# greenhousectrl-latest-monday-redo.net
KiCad netlist of a schematic drawn in EAGLE
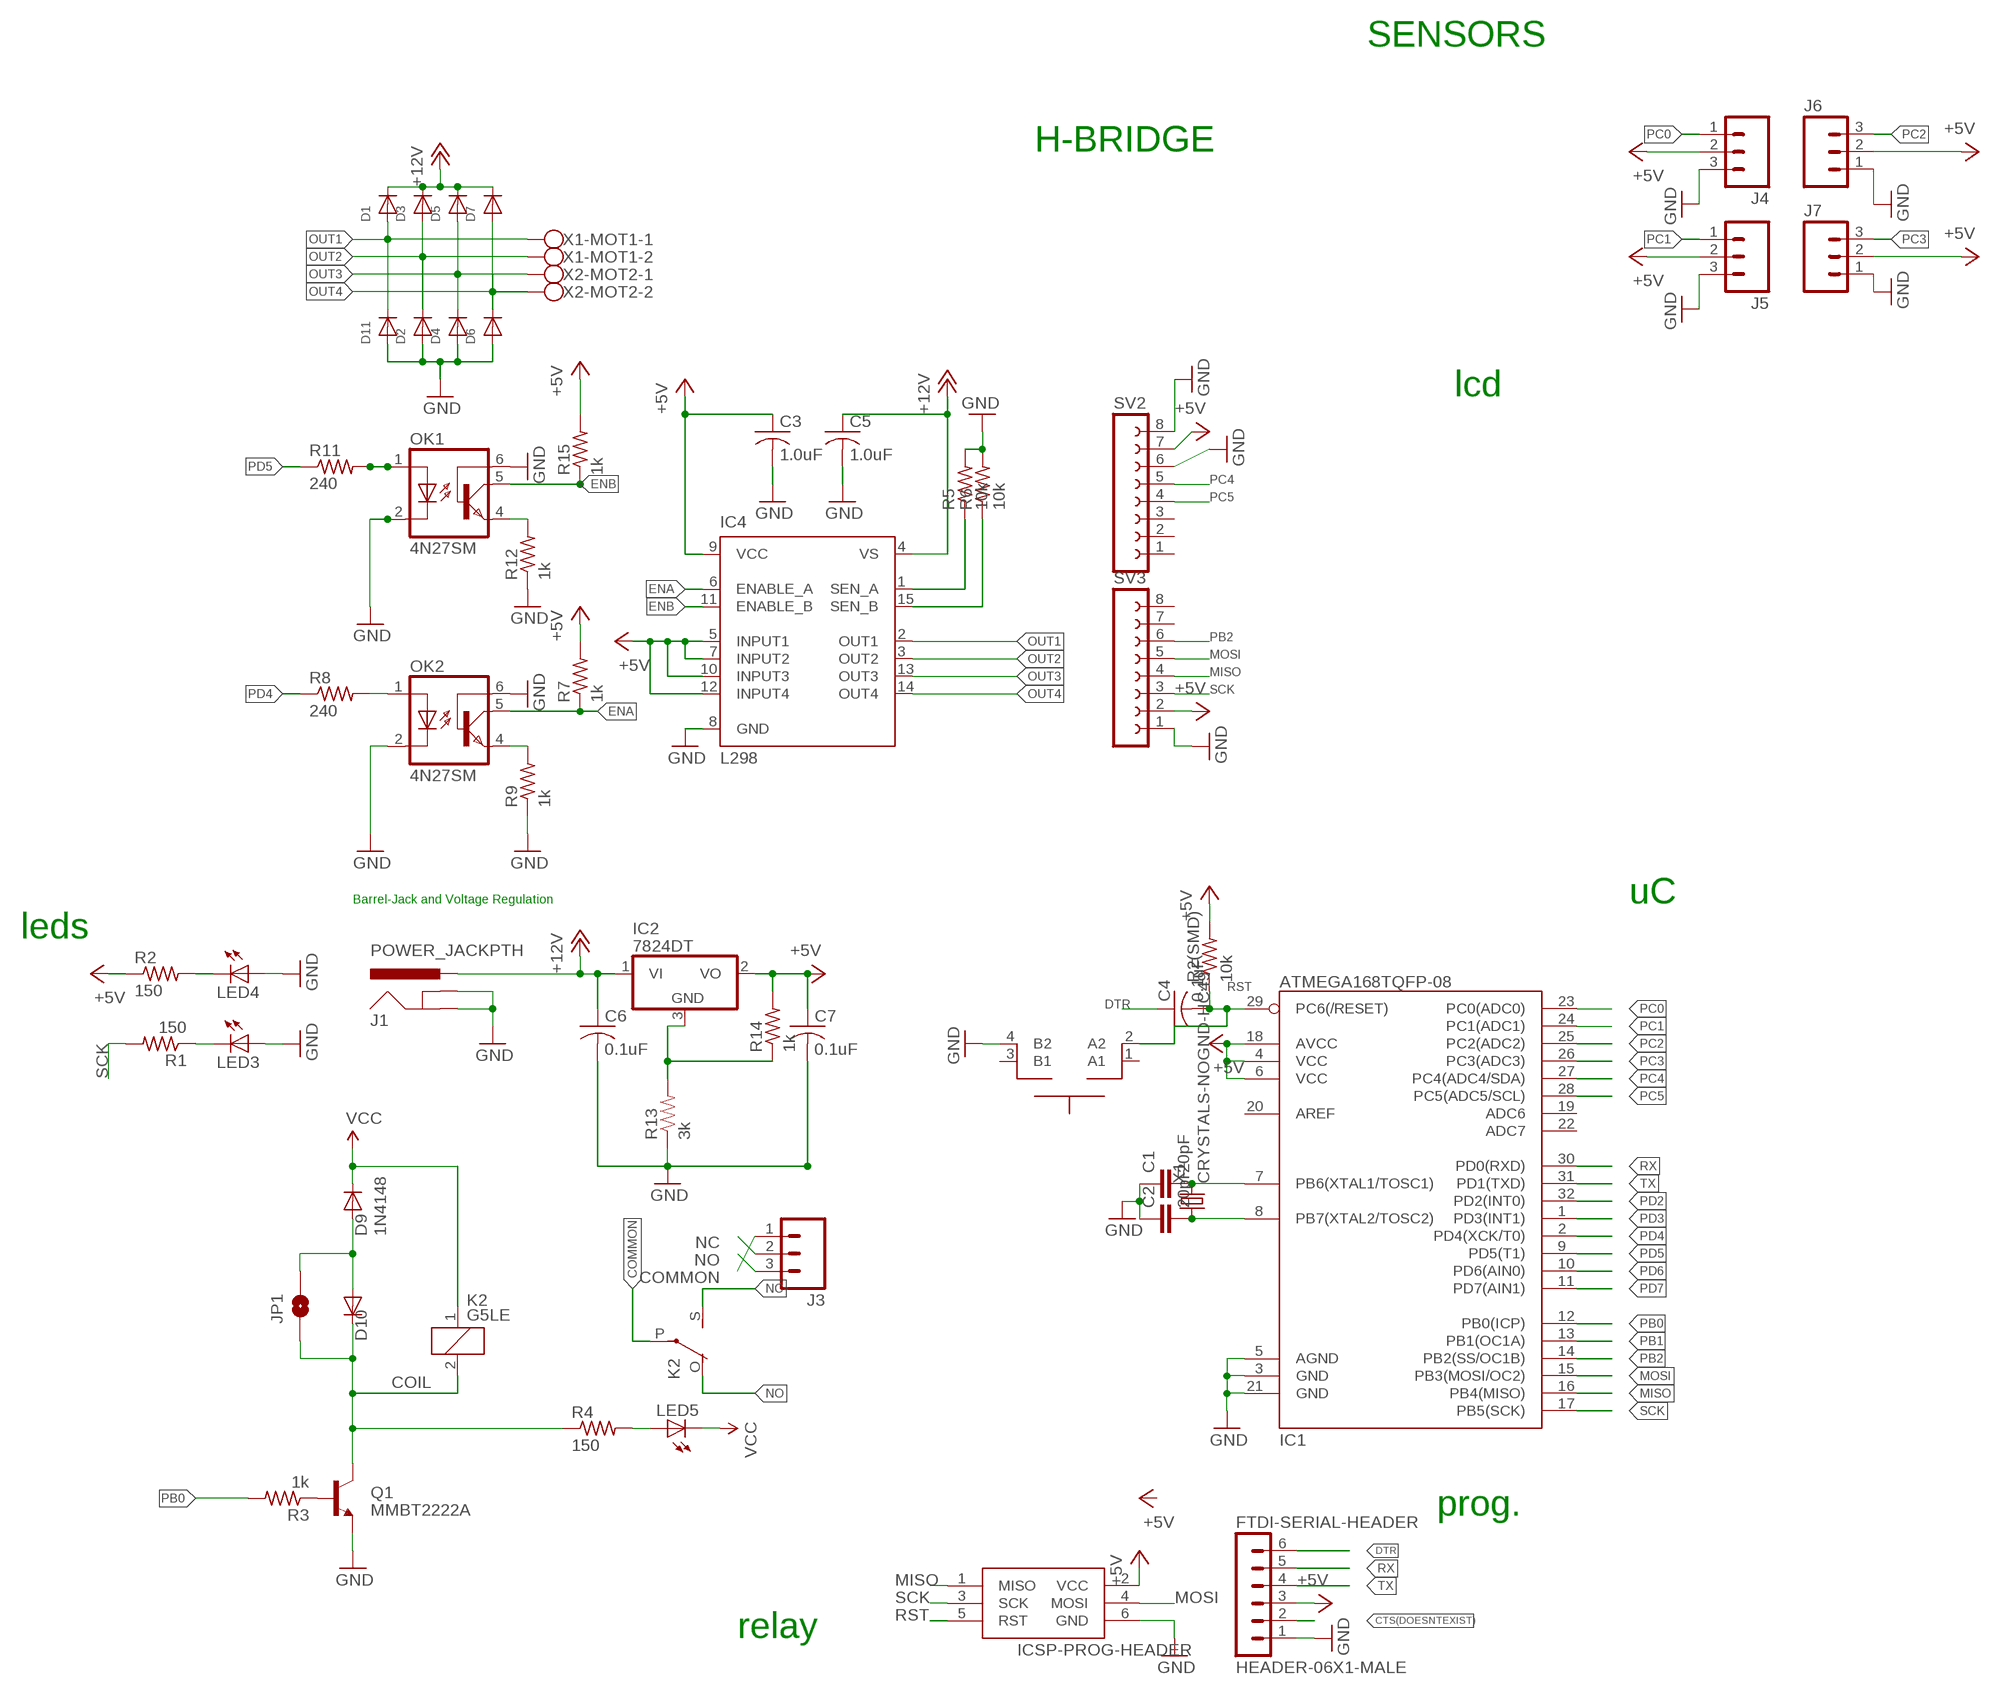
[diagram p0: schematic, sheet 1]

(export (version "E")
  (design (tool "Eeschema 10.0.6"))
  (components
    (comp (ref "C1")
      (value "20pF")
      (footprint "eagle-import:C0805")
      (libsource (lib "eagle-import") (part "C-EUC0805"))
    )
    (comp (ref "C2")
      (value "20pF")
      (footprint "eagle-import:C0805")
      (libsource (lib "eagle-import") (part "C-EUC0805"))
    )
    (comp (ref "C3")
      (value "1.0uF")
      (footprint "eagle-import:C0805")
      (libsource (lib "eagle-import") (part "C-USC0805"))
    )
    (comp (ref "C4")
      (value "0.1uF")
      (footprint "eagle-import:C0805")
      (libsource (lib "eagle-import") (part "C-USC0805"))
    )
    (comp (ref "C5")
      (value "1.0uF")
      (footprint "eagle-import:C0805")
      (libsource (lib "eagle-import") (part "C-USC0805"))
    )
    (comp (ref "C6")
      (value "0.1uF")
      (footprint "eagle-import:C0805")
      (libsource (lib "eagle-import") (part "C-USC0805"))
    )
    (comp (ref "C7")
      (value "0.1uF")
      (footprint "eagle-import:C0805")
      (libsource (lib "eagle-import") (part "C-USC0805"))
    )
    (comp (ref "D1")
      (value "DIODESOD-523")
      (footprint "eagle-import:SOD-523")
      (libsource (lib "eagle-import") (part "DIODESOD-523"))
    )
    (comp (ref "D2")
      (value "DIODESOD-523")
      (footprint "eagle-import:SOD-523")
      (libsource (lib "eagle-import") (part "DIODESOD-523"))
    )
    (comp (ref "D3")
      (value "DIODESOD-523")
      (footprint "eagle-import:SOD-523")
      (libsource (lib "eagle-import") (part "DIODESOD-523"))
    )
    (comp (ref "D4")
      (value "DIODESOD-523")
      (footprint "eagle-import:SOD-523")
      (libsource (lib "eagle-import") (part "DIODESOD-523"))
    )
    (comp (ref "D5")
      (value "DIODESOD-523")
      (footprint "eagle-import:SOD-523")
      (libsource (lib "eagle-import") (part "DIODESOD-523"))
    )
    (comp (ref "D6")
      (value "DIODESOD-523")
      (footprint "eagle-import:SOD-523")
      (libsource (lib "eagle-import") (part "DIODESOD-523"))
    )
    (comp (ref "D7")
      (value "DIODESOD-523")
      (footprint "eagle-import:SOD-523")
      (libsource (lib "eagle-import") (part "DIODESOD-523"))
    )
    (comp (ref "D9")
      (value "1N4148")
      (footprint "eagle-import:SOD-323F")
      (libsource (lib "eagle-import") (part "DIODESOD-323F"))
    )
    (comp (ref "D10")
      (value "Zener")
      (footprint "eagle-import:SOD-323F")
      (libsource (lib "eagle-import") (part "DIODESOD-323F"))
    )
    (comp (ref "D11")
      (value "DIODESOD-523")
      (footprint "eagle-import:SOD-523")
      (libsource (lib "eagle-import") (part "DIODESOD-523"))
    )
    (comp (ref "FTDI-SERIAL-HEADER")
      (value "HEADER-06X1-MALE")
      (footprint "eagle-import:06X1-PTH")
      (libsource (lib "eagle-import") (part "HEADER-06X1?-MALE"))
    )
    (comp (ref "IC1")
      (value "ATMEGA168TQFP-08")
      (footprint "eagle-import:TQFP32-08")
      (libsource (lib "eagle-import") (part "ATMEGA168TQFP-08"))
    )
    (comp (ref "IC2")
      (value "7824DT")
      (footprint "eagle-import:TO252")
      (libsource (lib "eagle-import") (part "78DT24"))
    )
    (comp (ref "IC4")
      (value "L298")
      (footprint "eagle-import:MULTIWATT-15")
      (fields (field (name "MPN") "L298N"))
      (libsource (lib "eagle-import") (part "L298"))
    )
    (comp (ref "ICSP-PROG-HEADER")
      (value "AVRISP-6")
      (footprint "eagle-import:AVRISP")
      (libsource (lib "eagle-import") (part "AVRISP-6"))
    )
    (comp (ref "J1")
      (value "POWER_JACKPTH")
      (footprint "eagle-import:POWER_JACK_PTH")
      (libsource (lib "eagle-import") (part "POWER_JACKPTH"))
    )
    (comp (ref "J3")
      (value "M03-SCREW-5MM")
      (footprint "eagle-import:SCREWTERMINAL-5MM-3")
      (libsource (lib "eagle-import") (part "M03-SCREW-5MM"))
    )
    (comp (ref "J4")
      (value "M03SCREW_LOCK")
      (footprint "eagle-import:SCREWTERMINAL-3.5MM-3_LOCK.007S")
      (libsource (lib "eagle-import") (part "M03SCREW_LOCK"))
    )
    (comp (ref "J5")
      (value "M03SCREW_LOCK")
      (footprint "eagle-import:SCREWTERMINAL-3.5MM-3_LOCK.007S")
      (libsource (lib "eagle-import") (part "M03SCREW_LOCK"))
    )
    (comp (ref "J6")
      (value "M03SCREW_LOCK")
      (footprint "eagle-import:SCREWTERMINAL-3.5MM-3_LOCK.007S")
      (libsource (lib "eagle-import") (part "M03SCREW_LOCK"))
    )
    (comp (ref "J7")
      (value "M03SCREW_LOCK")
      (footprint "eagle-import:SCREWTERMINAL-3.5MM-3_LOCK.007S")
      (libsource (lib "eagle-import") (part "M03SCREW_LOCK"))
    )
    (comp (ref "JP1")
      (value "JUMPER-PAD-2-NOYES_SILK")
      (footprint "eagle-import:PAD-JUMPER-2-NO_YES_SILK")
      (libsource (lib "eagle-import") (part "JUMPER-PAD-2-NOYES_SILK"))
    )
    (comp (ref "K2")
      (value "G5LE")
      (footprint "eagle-import:G5LE")
      (libsource (lib "eagle-import") (part "G5LE"))
    )
    (comp (ref "LED3")
      (value "LEDCHIP-LED0805")
      (footprint "eagle-import:CHIP-LED0805")
      (libsource (lib "eagle-import") (part "LEDCHIP-LED0805"))
    )
    (comp (ref "LED4")
      (value "LEDCHIP-LED0805")
      (footprint "eagle-import:CHIP-LED0805")
      (libsource (lib "eagle-import") (part "LEDCHIP-LED0805"))
    )
    (comp (ref "LED5")
      (value "LEDCHIP-LED0805")
      (footprint "eagle-import:CHIP-LED0805")
      (libsource (lib "eagle-import") (part "LEDCHIP-LED0805"))
    )
    (comp (ref "OK1")
      (value "4N27SM")
      (footprint "eagle-import:DIL6-SMD")
      (fields (field (name "MF") "FAIRCHILD SEMICONDUCTOR") (field (name "MPN") "4N27S-M"))
      (libsource (lib "eagle-import") (part "4N?MS27"))
    )
    (comp (ref "OK2")
      (value "4N27SM")
      (footprint "eagle-import:DIL6-SMD")
      (fields (field (name "MF") "FAIRCHILD SEMICONDUCTOR") (field (name "MPN") "4N27S-M"))
      (libsource (lib "eagle-import") (part "4N?MS27"))
    )
    (comp (ref "Q1")
      (value "MMBT2222A")
      (footprint "eagle-import:SOT23-3")
      (libsource (lib "eagle-import") (part "TRANSISTOR_NPNMMBT2222A"))
    )
    (comp (ref "R1")
      (value "150")
      (footprint "eagle-import:M0805")
      (libsource (lib "eagle-import") (part "R-US_M0805"))
    )
    (comp (ref "R2")
      (value "150")
      (footprint "eagle-import:M0805")
      (libsource (lib "eagle-import") (part "R-US_M0805"))
    )
    (comp (ref "R2(SMD)")
      (value "10k")
      (footprint "eagle-import:M0805")
      (libsource (lib "eagle-import") (part "R-US_M0805"))
    )
    (comp (ref "R3")
      (value "1k")
      (footprint "eagle-import:M0805")
      (libsource (lib "eagle-import") (part "R-US_M0805"))
    )
    (comp (ref "R4")
      (value "150")
      (footprint "eagle-import:M0805")
      (libsource (lib "eagle-import") (part "R-US_M0805"))
    )
    (comp (ref "R5")
      (value "10k")
      (footprint "eagle-import:M0805")
      (libsource (lib "eagle-import") (part "R-US_M0805"))
    )
    (comp (ref "R6")
      (value "10k")
      (footprint "eagle-import:M0805")
      (libsource (lib "eagle-import") (part "R-US_M0805"))
    )
    (comp (ref "R7")
      (value "1k")
      (footprint "eagle-import:M0805")
      (libsource (lib "eagle-import") (part "R-US_M0805"))
    )
    (comp (ref "R8")
      (value "240")
      (footprint "eagle-import:M0805")
      (libsource (lib "eagle-import") (part "R-US_M0805"))
    )
    (comp (ref "R9")
      (value "1k")
      (footprint "eagle-import:M0805")
      (libsource (lib "eagle-import") (part "R-US_M0805"))
    )
    (comp (ref "R11")
      (value "240")
      (footprint "eagle-import:M0805")
      (libsource (lib "eagle-import") (part "R-US_M0805"))
    )
    (comp (ref "R12")
      (value "1k")
      (footprint "eagle-import:M0805")
      (libsource (lib "eagle-import") (part "R-US_M0805"))
    )
    (comp (ref "R13")
      (value "3k")
      (footprint "eagle-import:0402-RES")
      (libsource (lib "eagle-import") (part "RESISTOR0402"))
    )
    (comp (ref "R14")
      (value "1k")
      (footprint "eagle-import:M0805")
      (libsource (lib "eagle-import") (part "R-US_M0805"))
    )
    (comp (ref "R15")
      (value "1k")
      (footprint "eagle-import:M0805")
      (libsource (lib "eagle-import") (part "R-US_M0805"))
    )
    (comp (ref "SV2")
      (value "FE08-1")
      (footprint "eagle-import:FE08")
      (libsource (lib "eagle-import") (part "FE08-1"))
    )
    (comp (ref "SV3")
      (value "FE08-1")
      (footprint "eagle-import:FE08")
      (libsource (lib "eagle-import") (part "FE08-1"))
    )
    (comp (ref "SW2")
      (value "MOMENTARYBUTTON")
      (footprint "eagle-import:SPST_NO_SMD")
      (libsource (lib "eagle-import") (part "MOMENTARYBUTTON"))
    )
    (comp (ref "X1")
      (value "CRYSTALS-NOGND-HC49")
      (footprint "eagle-import:HC49")
      (libsource (lib "eagle-import") (part "CRYSTALS-NOGND-HC49"))
    )
    (comp (ref "X1-MOT1")
      (value "W237-102")
      (footprint "eagle-import:W237-102")
      (fields (field (name "MPN") "237-102"))
      (libsource (lib "eagle-import") (part "W237-102"))
    )
    (comp (ref "X2-MOT2")
      (value "W237-102")
      (footprint "eagle-import:W237-102")
      (fields (field (name "MPN") "237-102"))
      (libsource (lib "eagle-import") (part "W237-102"))
    )
  )
  (nets
    (net (code "1") (name "+5V") (class "Default")
      (node (ref "C3") (pin "1") (pinfunction "1_1") (pintype "passive"))
      (node (ref "C7") (pin "1") (pinfunction "1_1") (pintype "passive"))
      (node (ref "FTDI-SERIAL-HEADER") (pin "3") (pinfunction "3_3") (pintype "passive"))
      (node (ref "IC1") (pin "18") (pinfunction "AVCC_18") (pintype "bidirectional"))
      (node (ref "IC1") (pin "4") (pinfunction "VCC_4") (pintype "bidirectional"))
      (node (ref "IC1") (pin "6") (pinfunction "VCC_6") (pintype "bidirectional"))
      (node (ref "IC2") (pin "2") (pinfunction "VO_2") (pintype "passive"))
      (node (ref "IC4") (pin "10") (pinfunction "INPUT3_10") (pintype "input"))
      (node (ref "IC4") (pin "12") (pinfunction "INPUT4_12") (pintype "input"))
      (node (ref "IC4") (pin "5") (pinfunction "INPUT1_5") (pintype "input"))
      (node (ref "IC4") (pin "7") (pinfunction "INPUT2_7") (pintype "input"))
      (node (ref "IC4") (pin "9") (pinfunction "VCC_9") (pintype "power_in"))
      (node (ref "ICSP-PROG-HEADER") (pin "2") (pinfunction "VCC_2") (pintype "power_in"))
      (node (ref "J4") (pin "2") (pinfunction "2_2") (pintype "passive"))
      (node (ref "J5") (pin "2") (pinfunction "2_2") (pintype "passive"))
      (node (ref "J6") (pin "2") (pinfunction "2_2") (pintype "passive"))
      (node (ref "J7") (pin "2") (pinfunction "2_2") (pintype "passive"))
      (node (ref "R14") (pin "2") (pinfunction "2_2") (pintype "passive"))
      (node (ref "R15") (pin "2") (pinfunction "2_2") (pintype "passive"))
      (node (ref "R2") (pin "1") (pinfunction "1_1") (pintype "passive"))
      (node (ref "R2(SMD)") (pin "2") (pinfunction "2_2") (pintype "passive"))
      (node (ref "R7") (pin "2") (pinfunction "2_2") (pintype "passive"))
      (node (ref "SV2") (pin "7") (pinfunction "7_7") (pintype "passive"))
      (node (ref "SV3") (pin "2") (pinfunction "2_2") (pintype "passive"))
    )
    (net (code "2") (name "+12V") (class "Default")
      (node (ref "C5") (pin "1") (pinfunction "1_1") (pintype "passive"))
      (node (ref "C6") (pin "1") (pinfunction "1_1") (pintype "passive"))
      (node (ref "D1") (pin "K") (pinfunction "C_K") (pintype "passive"))
      (node (ref "D3") (pin "K") (pinfunction "C_K") (pintype "passive"))
      (node (ref "D5") (pin "K") (pinfunction "C_K") (pintype "passive"))
      (node (ref "D7") (pin "K") (pinfunction "C_K") (pintype "passive"))
      (node (ref "IC2") (pin "1") (pinfunction "VI_1") (pintype "input"))
      (node (ref "IC4") (pin "4") (pinfunction "VS_4") (pintype "power_in"))
      (node (ref "J1") (pin "PWR") (pinfunction "PWR_PWR") (pintype "bidirectional"))
    )
    (net (code "3") (name "/COIL") (class "Default")
      (node (ref "D10") (pin "C") (pinfunction "C_C") (pintype "passive"))
      (node (ref "JP1") (pin "1") (pinfunction "1_1") (pintype "passive"))
      (node (ref "K2") (pin "2") (pinfunction "2_2") (pintype "passive"))
      (node (ref "Q1") (pin "3") (pinfunction "C_3") (pintype "passive"))
      (node (ref "R4") (pin "1") (pinfunction "1_1") (pintype "passive"))
    )
    (net (code "4") (name "/RST") (class "Default")
      (node (ref "C4") (pin "2") (pinfunction "2_2") (pintype "passive"))
      (node (ref "IC1") (pin "29") (pinfunction "PC6(/RESET)_29") (pintype "bidirectional"))
      (node (ref "ICSP-PROG-HEADER") (pin "5") (pinfunction "RST_5") (pintype "output"))
      (node (ref "R2(SMD)") (pin "1") (pinfunction "1_1") (pintype "passive"))
      (node (ref "SW2") (pin "2") (pinfunction "A2_2") (pintype "bidirectional"))
    )
    (net (code "5") (name "COMMON") (class "Default")
      (node (ref "J3") (pin "1") (pinfunction "1_1") (pintype "passive"))
      (node (ref "K2") (pin "P") (pinfunction "P_P") (pintype "passive"))
    )
    (net (code "6") (name "CTS(DOESNTEXIST)") (class "Default")
      (node (ref "FTDI-SERIAL-HEADER") (pin "2") (pinfunction "2_2") (pintype "passive"))
    )
    (net (code "7") (name "DTR") (class "Default")
      (node (ref "C4") (pin "1") (pinfunction "1_1") (pintype "passive"))
      (node (ref "FTDI-SERIAL-HEADER") (pin "6") (pinfunction "6_6") (pintype "passive"))
    )
    (net (code "8") (name "ENA") (class "Default")
      (node (ref "IC4") (pin "6") (pinfunction "ENABLE_A_6") (pintype "input"))
      (node (ref "OK2") (pin "5") (pinfunction "COL_5") (pintype "passive"))
      (node (ref "R7") (pin "1") (pinfunction "1_1") (pintype "passive"))
    )
    (net (code "9") (name "ENB") (class "Default")
      (node (ref "IC4") (pin "11") (pinfunction "ENABLE_B_11") (pintype "input"))
      (node (ref "OK1") (pin "5") (pinfunction "COL_5") (pintype "passive"))
      (node (ref "R15") (pin "1") (pinfunction "1_1") (pintype "passive"))
    )
    (net (code "10") (name "GND") (class "Default")
      (node (ref "C1") (pin "1") (pinfunction "1_1") (pintype "passive"))
      (node (ref "C2") (pin "1") (pinfunction "1_1") (pintype "passive"))
      (node (ref "C3") (pin "2") (pinfunction "2_2") (pintype "passive"))
      (node (ref "C5") (pin "2") (pinfunction "2_2") (pintype "passive"))
      (node (ref "C6") (pin "2") (pinfunction "2_2") (pintype "passive"))
      (node (ref "C7") (pin "2") (pinfunction "2_2") (pintype "passive"))
      (node (ref "D11") (pin "A") (pinfunction "A_A") (pintype "passive"))
      (node (ref "D2") (pin "A") (pinfunction "A_A") (pintype "passive"))
      (node (ref "D4") (pin "A") (pinfunction "A_A") (pintype "passive"))
      (node (ref "D6") (pin "A") (pinfunction "A_A") (pintype "passive"))
      (node (ref "FTDI-SERIAL-HEADER") (pin "1") (pinfunction "1_1") (pintype "passive"))
      (node (ref "IC1") (pin "21") (pinfunction "GND_21") (pintype "bidirectional"))
      (node (ref "IC1") (pin "3") (pinfunction "GND_3") (pintype "bidirectional"))
      (node (ref "IC1") (pin "5") (pinfunction "AGND_5") (pintype "bidirectional"))
      (node (ref "IC4") (pin "8") (pinfunction "GND_8") (pintype "power_in"))
      (node (ref "ICSP-PROG-HEADER") (pin "6") (pinfunction "GND_6") (pintype "power_in"))
      (node (ref "J1") (pin "GND") (pinfunction "GND_GND") (pintype "bidirectional"))
      (node (ref "J1") (pin "GNDBREAK") (pinfunction "GNDBREAK_GNDBREAK") (pintype "bidirectional"))
      (node (ref "J4") (pin "3") (pinfunction "3_3") (pintype "passive"))
      (node (ref "J5") (pin "3") (pinfunction "3_3") (pintype "passive"))
      (node (ref "J6") (pin "1") (pinfunction "1_1") (pintype "passive"))
      (node (ref "J7") (pin "1") (pinfunction "1_1") (pintype "passive"))
      (node (ref "LED3") (pin "A") (pinfunction "A_A") (pintype "passive"))
      (node (ref "LED4") (pin "A") (pinfunction "A_A") (pintype "passive"))
      (node (ref "OK1") (pin "2") (pinfunction "C_2") (pintype "passive"))
      (node (ref "OK1") (pin "6") (pinfunction "BAS_6") (pintype "passive"))
      (node (ref "OK2") (pin "2") (pinfunction "C_2") (pintype "passive"))
      (node (ref "OK2") (pin "6") (pinfunction "BAS_6") (pintype "passive"))
      (node (ref "Q1") (pin "2") (pinfunction "E_2") (pintype "passive"))
      (node (ref "R12") (pin "1") (pinfunction "1_1") (pintype "passive"))
      (node (ref "R13") (pin "1") (pinfunction "1_1") (pintype "passive"))
      (node (ref "R5") (pin "2") (pinfunction "2_2") (pintype "passive"))
      (node (ref "R6") (pin "2") (pinfunction "2_2") (pintype "passive"))
      (node (ref "R9") (pin "1") (pinfunction "1_1") (pintype "passive"))
      (node (ref "SV2") (pin "6") (pinfunction "6_6") (pintype "passive"))
      (node (ref "SV2") (pin "8") (pinfunction "8_8") (pintype "passive"))
      (node (ref "SV3") (pin "1") (pinfunction "1_1") (pintype "passive"))
      (node (ref "SW2") (pin "4") (pinfunction "B2_4") (pintype "bidirectional"))
    )
    (net (code "11") (name "MISO") (class "Default")
      (node (ref "IC1") (pin "16") (pinfunction "PB4(MISO)_16") (pintype "bidirectional"))
      (node (ref "ICSP-PROG-HEADER") (pin "1") (pinfunction "MISO_1") (pintype "input"))
      (node (ref "SV3") (pin "4") (pinfunction "4_4") (pintype "passive"))
    )
    (net (code "12") (name "MOSI") (class "Default")
      (node (ref "IC1") (pin "15") (pinfunction "PB3(MOSI/OC2)_15") (pintype "bidirectional"))
      (node (ref "ICSP-PROG-HEADER") (pin "4") (pinfunction "MOSI_4") (pintype "output"))
      (node (ref "SV3") (pin "5") (pinfunction "5_5") (pintype "passive"))
    )
    (net (code "13") (name "NC") (class "Default")
      (node (ref "J3") (pin "2") (pinfunction "2_2") (pintype "passive"))
      (node (ref "K2") (pin "S") (pinfunction "S_S") (pintype "passive"))
    )
    (net (code "14") (name "NO") (class "Default")
      (node (ref "J3") (pin "3") (pinfunction "3_3") (pintype "passive"))
      (node (ref "K2") (pin "O") (pinfunction "O_O") (pintype "passive"))
    )
    (net (code "15") (name "Net-(D10-PadA)") (class "Default")
      (node (ref "D10") (pin "A") (pinfunction "A_A") (pintype "passive"))
      (node (ref "D9") (pin "A") (pinfunction "A_A") (pintype "passive"))
      (node (ref "JP1") (pin "2") (pinfunction "2_2") (pintype "passive"))
    )
    (net (code "16") (name "Net-(IC1-PB6(XTAL1{slash}TOSC1))") (class "Default")
      (node (ref "C1") (pin "2") (pinfunction "2_2") (pintype "passive"))
      (node (ref "IC1") (pin "7") (pinfunction "PB6(XTAL1/TOSC1)_7") (pintype "bidirectional"))
      (node (ref "X1") (pin "2") (pinfunction "2_2") (pintype "passive"))
    )
    (net (code "17") (name "Net-(IC1-PB7(XTAL2{slash}TOSC2))") (class "Default")
      (node (ref "C2") (pin "2") (pinfunction "2_2") (pintype "passive"))
      (node (ref "IC1") (pin "8") (pinfunction "PB7(XTAL2/TOSC2)_8") (pintype "bidirectional"))
      (node (ref "X1") (pin "1") (pinfunction "1_1") (pintype "passive"))
    )
    (net (code "18") (name "Net-(IC2-GND)") (class "Default")
      (node (ref "IC2") (pin "3") (pinfunction "GND_3") (pintype "passive"))
      (node (ref "R13") (pin "2") (pinfunction "2_2") (pintype "passive"))
      (node (ref "R14") (pin "1") (pinfunction "1_1") (pintype "passive"))
    )
    (net (code "19") (name "Net-(IC4-SEN_A)") (class "Default")
      (node (ref "IC4") (pin "1") (pinfunction "SEN_A_1") (pintype "input"))
      (node (ref "R5") (pin "1") (pinfunction "1_1") (pintype "passive"))
    )
    (net (code "20") (name "Net-(IC4-SEN_B)") (class "Default")
      (node (ref "IC4") (pin "15") (pinfunction "SEN_B_15") (pintype "input"))
      (node (ref "R6") (pin "1") (pinfunction "1_1") (pintype "passive"))
    )
    (net (code "21") (name "Net-(LED3-PadC)") (class "Default")
      (node (ref "LED3") (pin "C") (pinfunction "C_C") (pintype "passive"))
      (node (ref "R1") (pin "1") (pinfunction "1_1") (pintype "passive"))
    )
    (net (code "22") (name "Net-(LED4-PadC)") (class "Default")
      (node (ref "LED4") (pin "C") (pinfunction "C_C") (pintype "passive"))
      (node (ref "R2") (pin "2") (pinfunction "2_2") (pintype "passive"))
    )
    (net (code "23") (name "Net-(LED5-PadA)") (class "Default")
      (node (ref "LED5") (pin "A") (pinfunction "A_A") (pintype "passive"))
      (node (ref "R4") (pin "2") (pinfunction "2_2") (pintype "passive"))
    )
    (net (code "24") (name "Net-(OK1-A)") (class "Default")
      (node (ref "OK1") (pin "1") (pinfunction "A_1") (pintype "passive"))
      (node (ref "R11") (pin "2") (pinfunction "2_2") (pintype "passive"))
    )
    (net (code "25") (name "Net-(OK1-EMI)") (class "Default")
      (node (ref "OK1") (pin "4") (pinfunction "EMI_4") (pintype "passive"))
      (node (ref "R12") (pin "2") (pinfunction "2_2") (pintype "passive"))
    )
    (net (code "26") (name "Net-(OK2-A)") (class "Default")
      (node (ref "OK2") (pin "1") (pinfunction "A_1") (pintype "passive"))
      (node (ref "R8") (pin "2") (pinfunction "2_2") (pintype "passive"))
    )
    (net (code "27") (name "Net-(OK2-EMI)") (class "Default")
      (node (ref "OK2") (pin "4") (pinfunction "EMI_4") (pintype "passive"))
      (node (ref "R9") (pin "2") (pinfunction "2_2") (pintype "passive"))
    )
    (net (code "28") (name "Net-(Q1-B)") (class "Default")
      (node (ref "Q1") (pin "1") (pinfunction "B_1") (pintype "passive"))
      (node (ref "R3") (pin "1") (pinfunction "1_1") (pintype "passive"))
    )
    (net (code "29") (name "OUT1") (class "Default")
      (node (ref "D1") (pin "A") (pinfunction "A_A") (pintype "passive"))
      (node (ref "D11") (pin "K") (pinfunction "C_K") (pintype "passive"))
      (node (ref "IC4") (pin "2") (pinfunction "OUT1_2") (pintype "output"))
      (node (ref "X1-MOT1") (pin "1") (pinfunction "KL_1") (pintype "passive"))
    )
    (net (code "30") (name "OUT2") (class "Default")
      (node (ref "D2") (pin "K") (pinfunction "C_K") (pintype "passive"))
      (node (ref "D3") (pin "A") (pinfunction "A_A") (pintype "passive"))
      (node (ref "IC4") (pin "3") (pinfunction "OUT2_3") (pintype "output"))
      (node (ref "X1-MOT1") (pin "2") (pinfunction "KL_2") (pintype "passive"))
    )
    (net (code "31") (name "OUT3") (class "Default")
      (node (ref "D4") (pin "K") (pinfunction "C_K") (pintype "passive"))
      (node (ref "D5") (pin "A") (pinfunction "A_A") (pintype "passive"))
      (node (ref "IC4") (pin "13") (pinfunction "OUT3_13") (pintype "output"))
      (node (ref "X2-MOT2") (pin "1") (pinfunction "KL_1") (pintype "passive"))
    )
    (net (code "32") (name "OUT4") (class "Default")
      (node (ref "D6") (pin "K") (pinfunction "C_K") (pintype "passive"))
      (node (ref "D7") (pin "A") (pinfunction "A_A") (pintype "passive"))
      (node (ref "IC4") (pin "14") (pinfunction "OUT4_14") (pintype "output"))
      (node (ref "X2-MOT2") (pin "2") (pinfunction "KL_2") (pintype "passive"))
    )
    (net (code "33") (name "PB0") (class "Default")
      (node (ref "IC1") (pin "12") (pinfunction "PB0(ICP)_12") (pintype "bidirectional"))
      (node (ref "R3") (pin "2") (pinfunction "2_2") (pintype "passive"))
    )
    (net (code "34") (name "PB1") (class "Default")
      (node (ref "IC1") (pin "13") (pinfunction "PB1(OC1A)_13") (pintype "bidirectional"))
    )
    (net (code "35") (name "PB2") (class "Default")
      (node (ref "IC1") (pin "14") (pinfunction "PB2(SS/OC1B)_14") (pintype "bidirectional"))
      (node (ref "SV3") (pin "6") (pinfunction "6_6") (pintype "passive"))
    )
    (net (code "36") (name "PC0") (class "Default")
      (node (ref "IC1") (pin "23") (pinfunction "PC0(ADC0)_23") (pintype "bidirectional"))
      (node (ref "J4") (pin "1") (pinfunction "1_1") (pintype "passive"))
    )
    (net (code "37") (name "PC1") (class "Default")
      (node (ref "IC1") (pin "24") (pinfunction "PC1(ADC1)_24") (pintype "bidirectional"))
      (node (ref "J5") (pin "1") (pinfunction "1_1") (pintype "passive"))
    )
    (net (code "38") (name "PC2") (class "Default")
      (node (ref "IC1") (pin "25") (pinfunction "PC2(ADC2)_25") (pintype "bidirectional"))
      (node (ref "J6") (pin "3") (pinfunction "3_3") (pintype "passive"))
    )
    (net (code "39") (name "PC3") (class "Default")
      (node (ref "IC1") (pin "26") (pinfunction "PC3(ADC3)_26") (pintype "bidirectional"))
      (node (ref "J7") (pin "3") (pinfunction "3_3") (pintype "passive"))
    )
    (net (code "40") (name "PC4") (class "Default")
      (node (ref "IC1") (pin "27") (pinfunction "PC4(ADC4/SDA)_27") (pintype "bidirectional"))
      (node (ref "SV2") (pin "5") (pinfunction "5_5") (pintype "passive"))
    )
    (net (code "41") (name "PC5") (class "Default")
      (node (ref "IC1") (pin "28") (pinfunction "PC5(ADC5/SCL)_28") (pintype "bidirectional"))
      (node (ref "SV2") (pin "4") (pinfunction "4_4") (pintype "passive"))
    )
    (net (code "42") (name "PD2") (class "Default")
      (node (ref "IC1") (pin "32") (pinfunction "PD2(INT0)_32") (pintype "bidirectional"))
    )
    (net (code "43") (name "PD3") (class "Default")
      (node (ref "IC1") (pin "1") (pinfunction "PD3(INT1)_1") (pintype "bidirectional"))
    )
    (net (code "44") (name "PD4") (class "Default")
      (node (ref "IC1") (pin "2") (pinfunction "PD4(XCK/T0)_2") (pintype "bidirectional"))
      (node (ref "R8") (pin "1") (pinfunction "1_1") (pintype "passive"))
    )
    (net (code "45") (name "PD5") (class "Default")
      (node (ref "IC1") (pin "9") (pinfunction "PD5(T1)_9") (pintype "bidirectional"))
      (node (ref "R11") (pin "1") (pinfunction "1_1") (pintype "passive"))
    )
    (net (code "46") (name "PD6") (class "Default")
      (node (ref "IC1") (pin "10") (pinfunction "PD6(AIN0)_10") (pintype "bidirectional"))
    )
    (net (code "47") (name "PD7") (class "Default")
      (node (ref "IC1") (pin "11") (pinfunction "PD7(AIN1)_11") (pintype "bidirectional"))
    )
    (net (code "48") (name "RX") (class "Default")
      (node (ref "FTDI-SERIAL-HEADER") (pin "5") (pinfunction "5_5") (pintype "passive"))
      (node (ref "IC1") (pin "30") (pinfunction "PD0(RXD)_30") (pintype "bidirectional"))
    )
    (net (code "49") (name "SCK") (class "Default")
      (node (ref "IC1") (pin "17") (pinfunction "PB5(SCK)_17") (pintype "bidirectional"))
      (node (ref "ICSP-PROG-HEADER") (pin "3") (pinfunction "SCK_3") (pintype "output"))
      (node (ref "R1") (pin "2") (pinfunction "2_2") (pintype "passive"))
      (node (ref "SV3") (pin "3") (pinfunction "3_3") (pintype "passive"))
    )
    (net (code "50") (name "TX") (class "Default")
      (node (ref "FTDI-SERIAL-HEADER") (pin "4") (pinfunction "4_4") (pintype "passive"))
      (node (ref "IC1") (pin "31") (pinfunction "PD1(TXD)_31") (pintype "bidirectional"))
    )
    (net (code "51") (name "VCC") (class "Default")
      (node (ref "D9") (pin "C") (pinfunction "C_C") (pintype "passive"))
      (node (ref "K2") (pin "1") (pinfunction "1_1") (pintype "passive"))
      (node (ref "LED5") (pin "C") (pinfunction "C_C") (pintype "passive"))
    )
    (net (code "52") (name "unconnected-(IC1-ADC6-Pad19)") (class "Default")
      (node (ref "IC1") (pin "19") (pinfunction "ADC6_19") (pintype "bidirectional"))
    )
    (net (code "53") (name "unconnected-(IC1-ADC7-Pad22)") (class "Default")
      (node (ref "IC1") (pin "22") (pinfunction "ADC7_22") (pintype "bidirectional"))
    )
    (net (code "54") (name "unconnected-(IC1-AREF-Pad20)") (class "Default")
      (node (ref "IC1") (pin "20") (pinfunction "AREF_20") (pintype "bidirectional"))
    )
    (net (code "55") (name "unconnected-(SV2-Pad1)") (class "Default")
      (node (ref "SV2") (pin "1") (pinfunction "1_1") (pintype "passive"))
    )
    (net (code "56") (name "unconnected-(SV2-Pad2)") (class "Default")
      (node (ref "SV2") (pin "2") (pinfunction "2_2") (pintype "passive"))
    )
    (net (code "57") (name "unconnected-(SV2-Pad3)") (class "Default")
      (node (ref "SV2") (pin "3") (pinfunction "3_3") (pintype "passive"))
    )
    (net (code "58") (name "unconnected-(SV3-Pad7)") (class "Default")
      (node (ref "SV3") (pin "7") (pinfunction "7_7") (pintype "passive"))
    )
    (net (code "59") (name "unconnected-(SV3-Pad8)") (class "Default")
      (node (ref "SV3") (pin "8") (pinfunction "8_8") (pintype "passive"))
    )
    (net (code "60") (name "unconnected-(SW2-A1-Pad1)") (class "Default")
      (node (ref "SW2") (pin "1") (pinfunction "A1_1") (pintype "bidirectional"))
    )
    (net (code "61") (name "unconnected-(SW2-B1-Pad3)") (class "Default")
      (node (ref "SW2") (pin "3") (pinfunction "B1_3") (pintype "bidirectional"))
    )
  )
)
